# LED_Indicator.net
KiCad netlist of a schematic drawn in EAGLE
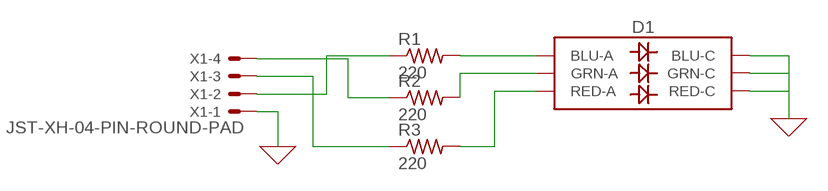
[diagram p0: schematic, sheet 1]

(export (version "E")
  (design (tool "Eeschema 10.0.6"))
  (components
    (comp (ref "D1")
      (value "LED-RGBBRG")
      (footprint "eagle-import:LED-TRICOLOR-5050")
      (libsource (lib "eagle-import") (part "LED-RGBBRG"))
    )
    (comp (ref "R1")
      (value "220")
      (footprint "eagle-import:R1206")
      (libsource (lib "eagle-import") (part "R-US_R1206"))
    )
    (comp (ref "R2")
      (value "220")
      (footprint "eagle-import:R1206")
      (libsource (lib "eagle-import") (part "R-US_R1206"))
    )
    (comp (ref "R3")
      (value "220")
      (footprint "eagle-import:R1206")
      (libsource (lib "eagle-import") (part "R-US_R1206"))
    )
    (comp (ref "X1")
      (value "JST-XH-04-PIN-ROUND-PAD")
      (footprint "eagle-import:JST-XH-04-PACKAGE-ROUND-PAD")
      (libsource (lib "eagle-import") (part "JST-XH-04-PIN-ROUND-PAD"))
    )
  )
  (nets
    (net (code "1") (name "GND") (class "Default")
      (node (ref "D1") (pin "1") (pinfunction "BLU-C_1") (pintype "bidirectional"))
      (node (ref "D1") (pin "2") (pinfunction "RED-C_2") (pintype "bidirectional"))
      (node (ref "D1") (pin "3") (pinfunction "GRN-C_3") (pintype "bidirectional"))
      (node (ref "X1") (pin "1") (pinfunction "S_1") (pintype "passive"))
    )
    (net (code "2") (name "Net-(D1-BLU-A)") (class "Default")
      (node (ref "D1") (pin "6") (pinfunction "BLU-A_6") (pintype "bidirectional"))
      (node (ref "R1") (pin "2") (pinfunction "2_2") (pintype "passive"))
    )
    (net (code "3") (name "Net-(D1-GRN-A)") (class "Default")
      (node (ref "D1") (pin "4") (pinfunction "GRN-A_4") (pintype "bidirectional"))
      (node (ref "R2") (pin "2") (pinfunction "2_2") (pintype "passive"))
    )
    (net (code "4") (name "Net-(D1-RED-A)") (class "Default")
      (node (ref "D1") (pin "5") (pinfunction "RED-A_5") (pintype "bidirectional"))
      (node (ref "R3") (pin "2") (pinfunction "2_2") (pintype "passive"))
    )
    (net (code "5") (name "Net-(X1B-S)") (class "Default")
      (node (ref "R1") (pin "1") (pinfunction "1_1") (pintype "passive"))
      (node (ref "X1") (pin "2") (pinfunction "S_2") (pintype "passive"))
    )
    (net (code "6") (name "Net-(X1C-S)") (class "Default")
      (node (ref "R3") (pin "1") (pinfunction "1_1") (pintype "passive"))
      (node (ref "X1") (pin "3") (pinfunction "S_3") (pintype "passive"))
    )
    (net (code "7") (name "Net-(X1D-S)") (class "Default")
      (node (ref "R2") (pin "1") (pinfunction "1_1") (pintype "passive"))
      (node (ref "X1") (pin "4") (pinfunction "S_4") (pintype "passive"))
    )
  )
)
